# target.net
KiCad netlist of a schematic drawn in Altium Designer
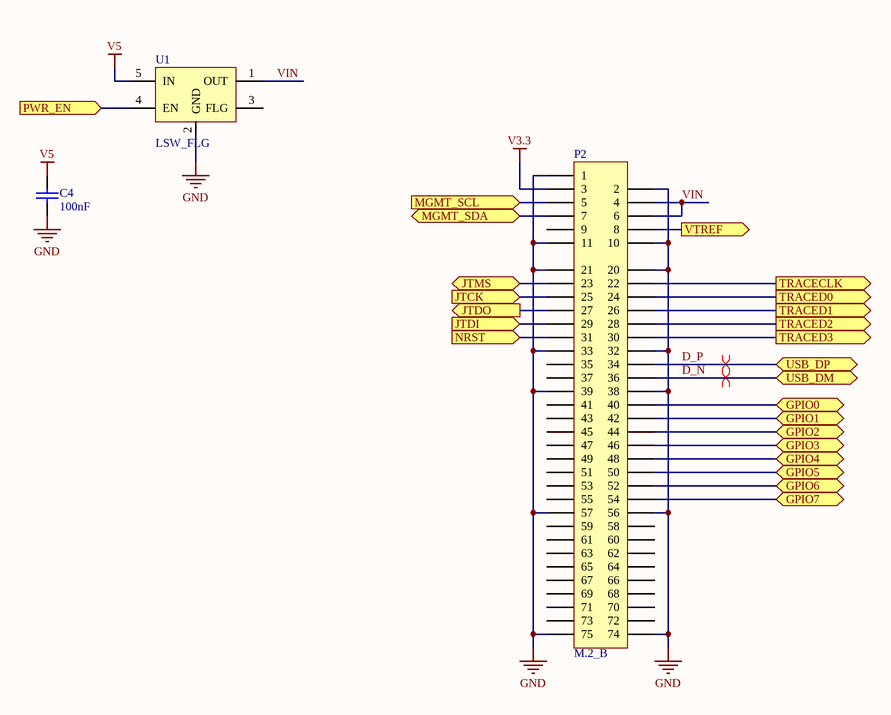
[diagram p0: target.SchDoc]

(export (version "E")
  (design (tool "Eeschema 10.0.6"))
  (components
    (comp (ref "C4") (value "100nF") (footprint "0402") (libsource (lib "misc") (part "Capacitor")))
    (comp (ref "P2") (value "M.2_B") (footprint "M.2_B") (libsource (lib "misc") (part "M.2_B")))
    (comp (ref "U1") (value "LSW_FLG") (footprint "SOT23-5") (libsource (lib "misc") (part "LSW_FLG")))
  )
  (nets
    (net (code "1") (name "/D_N") (class "Default")
      (node (ref "P2") (pin "36") (pinfunction "36_36") (pintype "passive"))
    )
    (net (code "2") (name "/D_P") (class "Default")
      (node (ref "P2") (pin "34") (pinfunction "34_34") (pintype "passive"))
    )
    (net (code "3") (name "/GPIO0") (class "Default")
      (node (ref "P2") (pin "40") (pinfunction "40_40") (pintype "passive"))
    )
    (net (code "4") (name "/GPIO1") (class "Default")
      (node (ref "P2") (pin "42") (pinfunction "42_42") (pintype "passive"))
    )
    (net (code "5") (name "/GPIO2") (class "Default")
      (node (ref "P2") (pin "44") (pinfunction "44_44") (pintype "passive"))
    )
    (net (code "6") (name "/GPIO3") (class "Default")
      (node (ref "P2") (pin "46") (pinfunction "46_46") (pintype "passive"))
    )
    (net (code "7") (name "/GPIO4") (class "Default")
      (node (ref "P2") (pin "48") (pinfunction "48_48") (pintype "passive"))
    )
    (net (code "8") (name "/GPIO5") (class "Default")
      (node (ref "P2") (pin "50") (pinfunction "50_50") (pintype "passive"))
    )
    (net (code "9") (name "/GPIO6") (class "Default")
      (node (ref "P2") (pin "52") (pinfunction "52_52") (pintype "passive"))
    )
    (net (code "10") (name "/GPIO7") (class "Default")
      (node (ref "P2") (pin "54") (pinfunction "54_54") (pintype "passive"))
    )
    (net (code "11") (name "/JTCK") (class "Default")
      (node (ref "P2") (pin "25") (pinfunction "25_25") (pintype "passive"))
    )
    (net (code "12") (name "/JTDI") (class "Default")
      (node (ref "P2") (pin "29") (pinfunction "29_29") (pintype "passive"))
    )
    (net (code "13") (name "/JTDO") (class "Default")
      (node (ref "P2") (pin "27") (pinfunction "27_27") (pintype "passive"))
    )
    (net (code "14") (name "/JTMS") (class "Default")
      (node (ref "P2") (pin "23") (pinfunction "23_23") (pintype "passive"))
    )
    (net (code "15") (name "/MGMT_SCL") (class "Default")
      (node (ref "P2") (pin "5") (pinfunction "5_5") (pintype "passive"))
    )
    (net (code "16") (name "/MGMT_SDA") (class "Default")
      (node (ref "P2") (pin "7") (pinfunction "7_7") (pintype "passive"))
    )
    (net (code "17") (name "/NRST") (class "Default")
      (node (ref "P2") (pin "31") (pinfunction "31_31") (pintype "passive"))
    )
    (net (code "18") (name "/PWR_EN") (class "Default")
      (node (ref "U1") (pin "4") (pinfunction "EN_4") (pintype "passive"))
    )
    (net (code "19") (name "/TRACECLK") (class "Default")
      (node (ref "P2") (pin "22") (pinfunction "22_22") (pintype "passive"))
    )
    (net (code "20") (name "/TRACED0") (class "Default")
      (node (ref "P2") (pin "24") (pinfunction "24_24") (pintype "passive"))
    )
    (net (code "21") (name "/TRACED1") (class "Default")
      (node (ref "P2") (pin "26") (pinfunction "26_26") (pintype "passive"))
    )
    (net (code "22") (name "/TRACED2") (class "Default")
      (node (ref "P2") (pin "28") (pinfunction "28_28") (pintype "passive"))
    )
    (net (code "23") (name "/TRACED3") (class "Default")
      (node (ref "P2") (pin "30") (pinfunction "30_30") (pintype "passive"))
    )
    (net (code "24") (name "/VIN") (class "Default")
      (node (ref "P2") (pin "4") (pinfunction "4_4") (pintype "passive"))
      (node (ref "P2") (pin "6") (pinfunction "6_6") (pintype "passive"))
      (node (ref "U1") (pin "1") (pinfunction "OUT_1") (pintype "passive"))
    )
    (net (code "25") (name "/VTREF") (class "Default")
      (node (ref "P2") (pin "8") (pinfunction "8_8") (pintype "passive"))
    )
    (net (code "26") (name "GND") (class "Default")
      (node (ref "C4") (pin "1") (pinfunction "1_1") (pintype "passive"))
      (node (ref "P2") (pin "1") (pinfunction "1_1") (pintype "passive"))
      (node (ref "P2") (pin "10") (pinfunction "10_10") (pintype "passive"))
      (node (ref "P2") (pin "11") (pinfunction "11_11") (pintype "passive"))
      (node (ref "P2") (pin "2") (pinfunction "2_2") (pintype "passive"))
      (node (ref "P2") (pin "20") (pinfunction "20_20") (pintype "passive"))
      (node (ref "P2") (pin "21") (pinfunction "21_21") (pintype "passive"))
      (node (ref "P2") (pin "32") (pinfunction "32_32") (pintype "passive"))
      (node (ref "P2") (pin "33") (pinfunction "33_33") (pintype "passive"))
      (node (ref "P2") (pin "38") (pinfunction "38_38") (pintype "passive"))
      (node (ref "P2") (pin "39") (pinfunction "39_39") (pintype "passive"))
      (node (ref "P2") (pin "56") (pinfunction "56_56") (pintype "passive"))
      (node (ref "P2") (pin "57") (pinfunction "57_57") (pintype "passive"))
      (node (ref "P2") (pin "74") (pinfunction "74_74") (pintype "passive"))
      (node (ref "P2") (pin "75") (pinfunction "75_75") (pintype "passive"))
      (node (ref "U1") (pin "2") (pinfunction "GND_2") (pintype "passive"))
    )
    (net (code "27") (name "V3.3") (class "Default")
      (node (ref "P2") (pin "3") (pinfunction "3_3") (pintype "passive"))
    )
    (net (code "28") (name "V5") (class "Default")
      (node (ref "C4") (pin "2") (pinfunction "2_2") (pintype "passive"))
      (node (ref "U1") (pin "5") (pinfunction "IN_5") (pintype "passive"))
    )
    (net (code "29") (name "unconnected-(P2-Pad9)") (class "Default")
      (node (ref "P2") (pin "9") (pinfunction "9_9") (pintype "passive"))
    )
    (net (code "30") (name "unconnected-(P2-Pad35)") (class "Default")
      (node (ref "P2") (pin "35") (pinfunction "35_35") (pintype "passive"))
    )
    (net (code "31") (name "unconnected-(P2-Pad37)") (class "Default")
      (node (ref "P2") (pin "37") (pinfunction "37_37") (pintype "passive"))
    )
    (net (code "32") (name "unconnected-(P2-Pad41)") (class "Default")
      (node (ref "P2") (pin "41") (pinfunction "41_41") (pintype "passive"))
    )
    (net (code "33") (name "unconnected-(P2-Pad43)") (class "Default")
      (node (ref "P2") (pin "43") (pinfunction "43_43") (pintype "passive"))
    )
    (net (code "34") (name "unconnected-(P2-Pad45)") (class "Default")
      (node (ref "P2") (pin "45") (pinfunction "45_45") (pintype "passive"))
    )
    (net (code "35") (name "unconnected-(P2-Pad47)") (class "Default")
      (node (ref "P2") (pin "47") (pinfunction "47_47") (pintype "passive"))
    )
    (net (code "36") (name "unconnected-(P2-Pad49)") (class "Default")
      (node (ref "P2") (pin "49") (pinfunction "49_49") (pintype "passive"))
    )
    (net (code "37") (name "unconnected-(P2-Pad51)") (class "Default")
      (node (ref "P2") (pin "51") (pinfunction "51_51") (pintype "passive"))
    )
    (net (code "38") (name "unconnected-(P2-Pad53)") (class "Default")
      (node (ref "P2") (pin "53") (pinfunction "53_53") (pintype "passive"))
    )
    (net (code "39") (name "unconnected-(P2-Pad55)") (class "Default")
      (node (ref "P2") (pin "55") (pinfunction "55_55") (pintype "passive"))
    )
    (net (code "40") (name "unconnected-(P2-Pad58)") (class "Default")
      (node (ref "P2") (pin "58") (pinfunction "58_58") (pintype "passive"))
    )
    (net (code "41") (name "unconnected-(P2-Pad59)") (class "Default")
      (node (ref "P2") (pin "59") (pinfunction "59_59") (pintype "passive"))
    )
    (net (code "42") (name "unconnected-(P2-Pad60)") (class "Default")
      (node (ref "P2") (pin "60") (pinfunction "60_60") (pintype "passive"))
    )
    (net (code "43") (name "unconnected-(P2-Pad61)") (class "Default")
      (node (ref "P2") (pin "61") (pinfunction "61_61") (pintype "passive"))
    )
    (net (code "44") (name "unconnected-(P2-Pad62)") (class "Default")
      (node (ref "P2") (pin "62") (pinfunction "62_62") (pintype "passive"))
    )
    (net (code "45") (name "unconnected-(P2-Pad63)") (class "Default")
      (node (ref "P2") (pin "63") (pinfunction "63_63") (pintype "passive"))
    )
    (net (code "46") (name "unconnected-(P2-Pad64)") (class "Default")
      (node (ref "P2") (pin "64") (pinfunction "64_64") (pintype "passive"))
    )
    (net (code "47") (name "unconnected-(P2-Pad65)") (class "Default")
      (node (ref "P2") (pin "65") (pinfunction "65_65") (pintype "passive"))
    )
    (net (code "48") (name "unconnected-(P2-Pad66)") (class "Default")
      (node (ref "P2") (pin "66") (pinfunction "66_66") (pintype "passive"))
    )
    (net (code "49") (name "unconnected-(P2-Pad67)") (class "Default")
      (node (ref "P2") (pin "67") (pinfunction "67_67") (pintype "passive"))
    )
    (net (code "50") (name "unconnected-(P2-Pad68)") (class "Default")
      (node (ref "P2") (pin "68") (pinfunction "68_68") (pintype "passive"))
    )
    (net (code "51") (name "unconnected-(P2-Pad69)") (class "Default")
      (node (ref "P2") (pin "69") (pinfunction "69_69") (pintype "passive"))
    )
    (net (code "52") (name "unconnected-(P2-Pad70)") (class "Default")
      (node (ref "P2") (pin "70") (pinfunction "70_70") (pintype "passive"))
    )
    (net (code "53") (name "unconnected-(P2-Pad71)") (class "Default")
      (node (ref "P2") (pin "71") (pinfunction "71_71") (pintype "passive"))
    )
    (net (code "54") (name "unconnected-(P2-Pad72)") (class "Default")
      (node (ref "P2") (pin "72") (pinfunction "72_72") (pintype "passive"))
    )
    (net (code "55") (name "unconnected-(P2-Pad73)") (class "Default")
      (node (ref "P2") (pin "73") (pinfunction "73_73") (pintype "passive"))
    )
    (net (code "56") (name "unconnected-(U1-FLG-Pad3)") (class "Default")
      (node (ref "U1") (pin "3") (pinfunction "FLG_3") (pintype "passive"))
    )
  )
)
